# naked.net
KiCad netlist of a schematic drawn in EAGLE
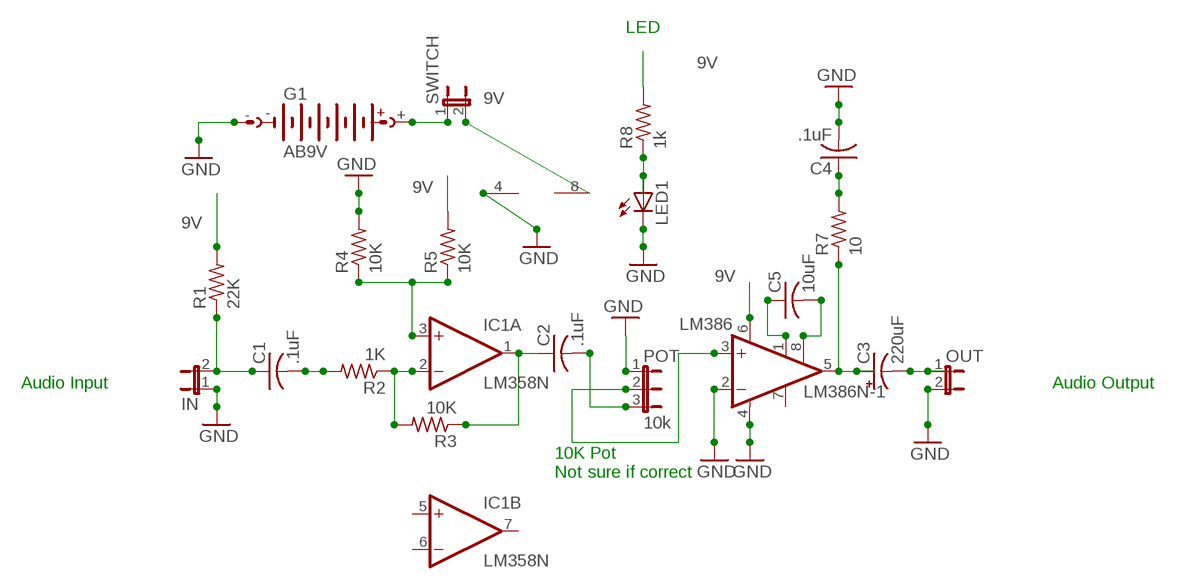
[diagram p0: schematic, sheet 1]

(export (version "E")
  (design (tool "Eeschema 10.0.6"))
  (components
    (comp (ref "C1")
      (value ".1uF")
      (footprint "eagle-import:C025-024X044")
      (libsource (lib "eagle-import") (part "C-US025-024X044"))
    )
    (comp (ref "C2")
      (value ".1uF")
      (footprint "eagle-import:C025-024X044")
      (libsource (lib "eagle-import") (part "C-US025-024X044"))
    )
    (comp (ref "C3")
      (value "220uF")
      (footprint "eagle-import:E3,5-8")
      (libsource (lib "eagle-import") (part "CPOL-USE3.5-8"))
    )
    (comp (ref "C4")
      (value ".1uF")
      (footprint "eagle-import:C025-024X044")
      (libsource (lib "eagle-import") (part "C-US025-024X044"))
    )
    (comp (ref "C5")
      (value "10uF")
      (footprint "eagle-import:C025-024X044")
      (libsource (lib "eagle-import") (part "C-US025-024X044"))
    )
    (comp (ref "G1")
      (value "AB9V")
      (footprint "eagle-import:AB9V")
      (libsource (lib "eagle-import") (part "AB9V"))
    )
    (comp (ref "IC1")
      (value "LM358N")
      (footprint "eagle-import:DIL08")
      (libsource (lib "eagle-import") (part "LM358N"))
    )
    (comp (ref "IN")
      (value "JP1E")
      (footprint "eagle-import:JP1")
      (libsource (lib "eagle-import") (part "JP1E"))
    )
    (comp (ref "LED1")
      (value "LED5MM")
      (footprint "eagle-import:LED5MM")
      (libsource (lib "eagle-import") (part "LED5MM"))
    )
    (comp (ref "LM386")
      (value "LM386N-1")
      (footprint "eagle-import:DIL08")
      (libsource (lib "eagle-import") (part "LM386?-N1"))
    )
    (comp (ref "OUT")
      (value "JP1E")
      (footprint "eagle-import:JP1")
      (libsource (lib "eagle-import") (part "JP1E"))
    )
    (comp (ref "POT")
      (value "10k")
      (footprint "eagle-import:JP2")
      (libsource (lib "eagle-import") (part "JP2E"))
    )
    (comp (ref "R1")
      (value "22K")
      (footprint "eagle-import:0204_7")
      (libsource (lib "eagle-import") (part "R-US_0204/7"))
    )
    (comp (ref "R2")
      (value "1K")
      (footprint "eagle-import:0204_7")
      (libsource (lib "eagle-import") (part "R-US_0204/7"))
    )
    (comp (ref "R3")
      (value "10K")
      (footprint "eagle-import:0204_7")
      (libsource (lib "eagle-import") (part "R-US_0204/7"))
    )
    (comp (ref "R4")
      (value "10K")
      (footprint "eagle-import:0204_7")
      (libsource (lib "eagle-import") (part "R-US_0204/7"))
    )
    (comp (ref "R5")
      (value "10K")
      (footprint "eagle-import:0204_7")
      (libsource (lib "eagle-import") (part "R-US_0204/7"))
    )
    (comp (ref "R7")
      (value "10")
      (footprint "eagle-import:0204_7")
      (libsource (lib "eagle-import") (part "R-US_0204/7"))
    )
    (comp (ref "R8")
      (value "1k")
      (footprint "eagle-import:0204_7")
      (libsource (lib "eagle-import") (part "R-US_0204/7"))
    )
    (comp (ref "SWITCH")
      (value "JP1E")
      (footprint "eagle-import:JP1")
      (libsource (lib "eagle-import") (part "JP1E"))
    )
  )
  (nets
    (net (code "1") (name "/9V") (class "Default")
      (node (ref "IC1") (pin "8") (pinfunction "V+_8") (pintype "power_in"))
      (node (ref "LM386") (pin "6") (pinfunction "VS_6") (pintype "power_in"))
      (node (ref "R1") (pin "2") (pinfunction "2_2") (pintype "passive"))
      (node (ref "R5") (pin "2") (pinfunction "2_2") (pintype "passive"))
      (node (ref "R8") (pin "2") (pinfunction "2_2") (pintype "passive"))
      (node (ref "SWITCH") (pin "2") (pinfunction "2_2") (pintype "passive"))
    )
    (net (code "2") (name "GND") (class "Default")
      (node (ref "C4") (pin "2") (pinfunction "2_2") (pintype "passive"))
      (node (ref "G1") (pin "-") (pinfunction "-_-") (pintype "passive"))
      (node (ref "IC1") (pin "4") (pinfunction "V-_4") (pintype "power_in"))
      (node (ref "IN") (pin "1") (pinfunction "1_1") (pintype "passive"))
      (node (ref "LED1") (pin "K") (pinfunction "C_K") (pintype "passive"))
      (node (ref "LM386") (pin "2") (pinfunction "-IN_2") (pintype "input"))
      (node (ref "LM386") (pin "4") (pinfunction "GND_4") (pintype "power_in"))
      (node (ref "OUT") (pin "2") (pinfunction "2_2") (pintype "passive"))
      (node (ref "POT") (pin "1") (pinfunction "1_1") (pintype "passive"))
      (node (ref "R4") (pin "2") (pinfunction "2_2") (pintype "passive"))
    )
    (net (code "3") (name "Net-(C1-Pad1)") (class "Default")
      (node (ref "C1") (pin "1") (pinfunction "1_1") (pintype "passive"))
      (node (ref "IN") (pin "2") (pinfunction "2_2") (pintype "passive"))
      (node (ref "R1") (pin "1") (pinfunction "1_1") (pintype "passive"))
    )
    (net (code "4") (name "Net-(C1-Pad2)") (class "Default")
      (node (ref "C1") (pin "2") (pinfunction "2_2") (pintype "passive"))
      (node (ref "R2") (pin "2") (pinfunction "2_2") (pintype "passive"))
    )
    (net (code "5") (name "Net-(C2-Pad2)") (class "Default")
      (node (ref "C2") (pin "2") (pinfunction "2_2") (pintype "passive"))
      (node (ref "POT") (pin "3") (pinfunction "3_3") (pintype "passive"))
    )
    (net (code "6") (name "Net-(C3-Pad-)") (class "Default")
      (node (ref "C3") (pin "-") (pinfunction "-_-") (pintype "passive"))
      (node (ref "OUT") (pin "1") (pinfunction "1_1") (pintype "passive"))
    )
    (net (code "7") (name "Net-(C4-Pad1)") (class "Default")
      (node (ref "C4") (pin "1") (pinfunction "1_1") (pintype "passive"))
      (node (ref "R7") (pin "2") (pinfunction "2_2") (pintype "passive"))
    )
    (net (code "8") (name "Net-(C5-Pad1)") (class "Default")
      (node (ref "C5") (pin "1") (pinfunction "1_1") (pintype "passive"))
      (node (ref "LM386") (pin "1") (pinfunction "GAIN_1") (pintype "passive"))
    )
    (net (code "9") (name "Net-(C5-Pad2)") (class "Default")
      (node (ref "C5") (pin "2") (pinfunction "2_2") (pintype "passive"))
      (node (ref "LM386") (pin "8") (pinfunction "GAIN_8") (pintype "passive"))
    )
    (net (code "10") (name "Net-(G1-Pad+)") (class "Default")
      (node (ref "G1") (pin "+") (pinfunction "+_+") (pintype "passive"))
      (node (ref "SWITCH") (pin "1") (pinfunction "1_1") (pintype "passive"))
    )
    (net (code "11") (name "Net-(IC1A-+IN)") (class "Default")
      (node (ref "IC1") (pin "3") (pinfunction "+IN_3") (pintype "input"))
      (node (ref "R4") (pin "1") (pinfunction "1_1") (pintype "passive"))
      (node (ref "R5") (pin "1") (pinfunction "1_1") (pintype "passive"))
    )
    (net (code "12") (name "Net-(IC1A--IN)") (class "Default")
      (node (ref "IC1") (pin "2") (pinfunction "-IN_2") (pintype "input"))
      (node (ref "R2") (pin "1") (pinfunction "1_1") (pintype "passive"))
      (node (ref "R3") (pin "2") (pinfunction "2_2") (pintype "passive"))
    )
    (net (code "13") (name "Net-(IC1A-OUT)") (class "Default")
      (node (ref "C2") (pin "1") (pinfunction "1_1") (pintype "passive"))
      (node (ref "IC1") (pin "1") (pinfunction "OUT_1") (pintype "output"))
      (node (ref "R3") (pin "1") (pinfunction "1_1") (pintype "passive"))
    )
    (net (code "14") (name "Net-(LED1-PadA)") (class "Default")
      (node (ref "LED1") (pin "A") (pinfunction "A_A") (pintype "passive"))
      (node (ref "R8") (pin "1") (pinfunction "1_1") (pintype "passive"))
    )
    (net (code "15") (name "Net-(LM386-+IN)") (class "Default")
      (node (ref "LM386") (pin "3") (pinfunction "+IN_3") (pintype "input"))
      (node (ref "POT") (pin "2") (pinfunction "2_2") (pintype "passive"))
    )
    (net (code "16") (name "Net-(LM386-OUT)") (class "Default")
      (node (ref "C3") (pin "+") (pinfunction "+_+") (pintype "passive"))
      (node (ref "LM386") (pin "5") (pinfunction "OUT_5") (pintype "output"))
      (node (ref "R7") (pin "1") (pinfunction "1_1") (pintype "passive"))
    )
    (net (code "17") (name "unconnected-(IC1B-+IN-Pad5)") (class "Default")
      (node (ref "IC1") (pin "5") (pinfunction "+IN_5") (pintype "input"))
    )
    (net (code "18") (name "unconnected-(IC1B--IN-Pad6)") (class "Default")
      (node (ref "IC1") (pin "6") (pinfunction "-IN_6") (pintype "input"))
    )
    (net (code "19") (name "unconnected-(IC1B-OUT-Pad7)") (class "Default")
      (node (ref "IC1") (pin "7") (pinfunction "OUT_7") (pintype "output"))
    )
    (net (code "20") (name "unconnected-(LM386-BYPASS-Pad7)") (class "Default")
      (node (ref "LM386") (pin "7") (pinfunction "BYPASS_7") (pintype "passive"))
    )
  )
)
